# Power_Selection_-_Temperature_Sense.net
KiCad netlist of a schematic drawn in Altium Designer
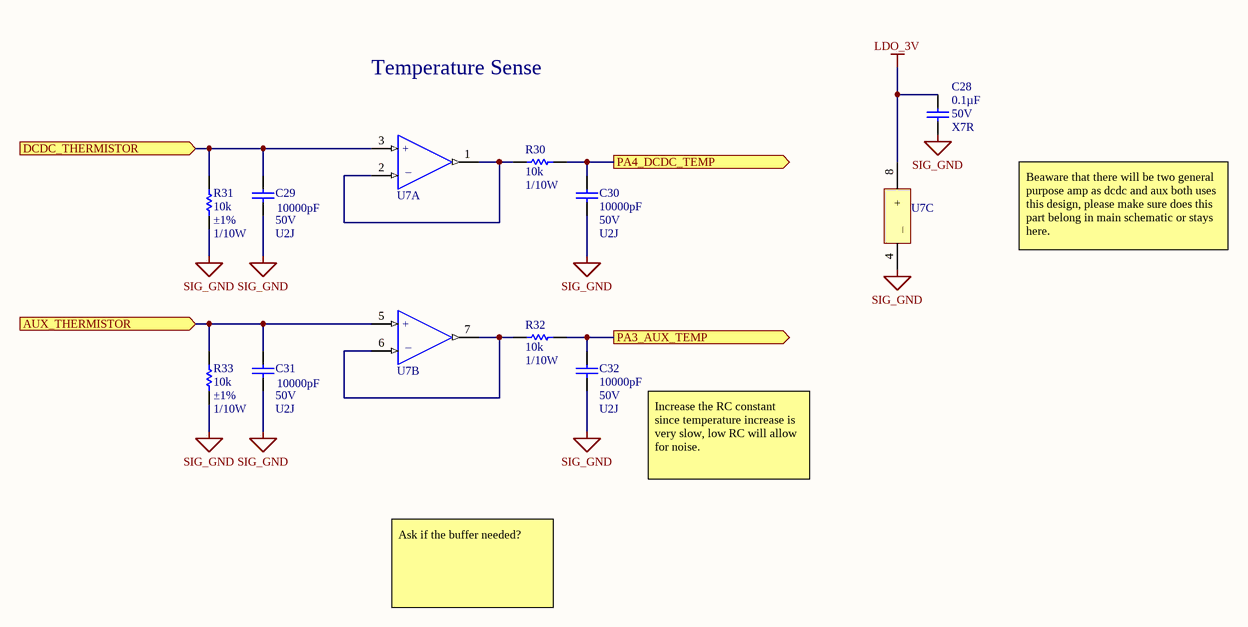
[diagram p0: Power Selection - Temperature Sense.SchDoc]

(export (version "E")
  (design (tool "Eeschema 10.0.6"))
  (components
    (comp (ref "C28")
      (value "CAP CER 0.1UF 50V 10% X7R 0603")
      (footprint "CAP, 0603")
      (description "0.10µF ±10% 50V Ceramic Capacitor X7R 0603 (1608 Metric)")
      (fields
        (field (name "TOLERANCE") "±10%")
        (field (name "CAPACITANCE") "0.1µF")
        (field (name "VOLTAGE") "50V")
        (field (name "TEMPERATURE COEFFICIENT") "X7R")
      )
      (libsource (lib "Schematic Diagrams") (part "CAP CER 0.1UF 50V 10% X7R 0603"))
    )
    (comp (ref "C29")
      (value "CAP CER 10nF 50V 5% X7R 0603")
      (footprint "CAP, 0603")
      (description "10000pF ±5% 50V Ceramic Capacitor U2J 0603 (1608 Metric)")
      (fields
        (field (name "TOLERANCE") "±5%")
        (field (name "CAPACITANCE") "10000pF")
        (field (name "VOLTAGE") "50V")
        (field (name "TEMPERATURE COEFFICIENT") "U2J")
      )
      (libsource (lib "Schematic Diagrams") (part "CAP CER 10nF 50V 5% X7R 0603"))
    )
    (comp (ref "C30")
      (value "CAP CER 10nF 50V 5% X7R 0603")
      (footprint "CAP, 0603")
      (description "10000pF ±5% 50V Ceramic Capacitor U2J 0603 (1608 Metric)")
      (fields
        (field (name "TOLERANCE") "±5%")
        (field (name "CAPACITANCE") "10000pF")
        (field (name "VOLTAGE") "50V")
        (field (name "TEMPERATURE COEFFICIENT") "U2J")
      )
      (libsource (lib "Schematic Diagrams") (part "CAP CER 10nF 50V 5% X7R 0603"))
    )
    (comp (ref "C31")
      (value "CAP CER 10nF 50V 5% X7R 0603")
      (footprint "CAP, 0603")
      (description "10000pF ±5% 50V Ceramic Capacitor U2J 0603 (1608 Metric)")
      (fields
        (field (name "TOLERANCE") "±5%")
        (field (name "CAPACITANCE") "10000pF")
        (field (name "VOLTAGE") "50V")
        (field (name "TEMPERATURE COEFFICIENT") "U2J")
      )
      (libsource (lib "Schematic Diagrams") (part "CAP CER 10nF 50V 5% X7R 0603"))
    )
    (comp (ref "C32")
      (value "CAP CER 10nF 50V 5% X7R 0603")
      (footprint "CAP, 0603")
      (description "10000pF ±5% 50V Ceramic Capacitor U2J 0603 (1608 Metric)")
      (fields
        (field (name "TOLERANCE") "±5%")
        (field (name "CAPACITANCE") "10000pF")
        (field (name "VOLTAGE") "50V")
        (field (name "TEMPERATURE COEFFICIENT") "U2J")
      )
      (libsource (lib "Schematic Diagrams") (part "CAP CER 10nF 50V 5% X7R 0603"))
    )
    (comp (ref "R30")
      (value "RES 10K OHM 1% 1/10W 0603")
      (footprint "RES, 0603")
      (description "RES SMD 10K OHM 1% 1/10W 0603")
      (fields
        (field (name "TOLERANCE") "±1%")
        (field (name "RESISTANCE") "10k")
        (field (name "POWER") "1/10W")
      )
      (libsource (lib "Schematic Diagrams") (part "RES 10K OHM 1% 1/10W 0603"))
    )
    (comp (ref "R31")
      (value "RES 10K OHM 1% 1/10W 0603")
      (footprint "RES, 0603")
      (description "RES SMD 10K OHM 1% 1/10W 0603")
      (fields
        (field (name "RESISTANCE") "10k")
        (field (name "TOLERANCE") "±1%")
        (field (name "POWER") "1/10W")
      )
      (libsource (lib "Schematic Diagrams") (part "RES 10K OHM 1% 1/10W 0603"))
    )
    (comp (ref "R32")
      (value "RES 10K OHM 1% 1/10W 0603")
      (footprint "RES, 0603")
      (description "RES SMD 10K OHM 1% 1/10W 0603")
      (fields
        (field (name "TOLERANCE") "±1%")
        (field (name "RESISTANCE") "10k")
        (field (name "POWER") "1/10W")
      )
      (libsource (lib "Schematic Diagrams") (part "RES 10K OHM 1% 1/10W 0603"))
    )
    (comp (ref "R33")
      (value "RES 10K OHM 1% 1/10W 0603")
      (footprint "RES, 0603")
      (description "RES SMD 10K OHM 1% 1/10W 0603")
      (fields
        (field (name "RESISTANCE") "10k")
        (field (name "TOLERANCE") "±1%")
        (field (name "POWER") "1/10W")
      )
      (libsource (lib "Schematic Diagrams") (part "RES 10K OHM 1% 1/10W 0603"))
    )
    (comp (ref "U7")
      (value "IC OP AMP DUAL GP RR 10MHZ 8-VSSOP")
      (footprint "IC DUAL OPAMP OPA2197 8-VSSOP")
      (description "General Purpose Amplifier 2 Circuit Rail-to-Rail 8-VSSOP")
      (fields
        (field (name "MANUFACTURER") "Texas Instruments")
        (field (name "MANUFACTURER PART NUMBER") "OPA2197IDGKR")
      )
      (libsource (lib "Schematic Diagrams") (part "IC OP AMP DUAL GP RR 10MHZ 8-VSSOP"))
    )
  )
  (nets
    (net (code "1") (name "/AUX_THERMISTOR") (class "Default")
      (node (ref "C31") (pin "1") (pinfunction "1_1") (pintype "passive"))
      (node (ref "R33") (pin "1") (pinfunction "1_1") (pintype "passive"))
      (node (ref "U7") (pin "5") (pinfunction "+IN_B_5") (pintype "input"))
    )
    (net (code "2") (name "/DCDC_THERMISTOR") (class "Default")
      (node (ref "C29") (pin "1") (pinfunction "1_1") (pintype "passive"))
      (node (ref "R31") (pin "1") (pinfunction "1_1") (pintype "passive"))
      (node (ref "U7") (pin "3") (pinfunction "+IN_A_3") (pintype "input"))
    )
    (net (code "3") (name "/PA3_AUX_TEMP") (class "Default")
      (node (ref "C32") (pin "1") (pinfunction "1_1") (pintype "passive"))
      (node (ref "R32") (pin "2") (pinfunction "2_2") (pintype "passive"))
    )
    (net (code "4") (name "/PA4_DCDC_TEMP") (class "Default")
      (node (ref "C30") (pin "1") (pinfunction "1_1") (pintype "passive"))
      (node (ref "R30") (pin "2") (pinfunction "2_2") (pintype "passive"))
    )
    (net (code "5") (name "LDO_3V") (class "Default")
      (node (ref "C28") (pin "1") (pinfunction "1_1") (pintype "passive"))
      (node (ref "U7") (pin "8") (pinfunction "+_8") (pintype "power_in"))
    )
    (net (code "6") (name "Net-(U7A--IN_A)") (class "Default")
      (node (ref "R30") (pin "1") (pinfunction "1_1") (pintype "passive"))
      (node (ref "U7") (pin "1") (pinfunction "OUT_A_1") (pintype "output"))
      (node (ref "U7") (pin "2") (pinfunction "-IN_A_2") (pintype "input"))
    )
    (net (code "7") (name "Net-(U7B--IN_B)") (class "Default")
      (node (ref "R32") (pin "1") (pinfunction "1_1") (pintype "passive"))
      (node (ref "U7") (pin "6") (pinfunction "-IN_B_6") (pintype "input"))
      (node (ref "U7") (pin "7") (pinfunction "OUT_B_7") (pintype "output"))
    )
    (net (code "8") (name "SIG_GND") (class "Default")
      (node (ref "C28") (pin "2") (pinfunction "2_2") (pintype "passive"))
      (node (ref "C29") (pin "2") (pinfunction "2_2") (pintype "passive"))
      (node (ref "C30") (pin "2") (pinfunction "2_2") (pintype "passive"))
      (node (ref "C31") (pin "2") (pinfunction "2_2") (pintype "passive"))
      (node (ref "C32") (pin "2") (pinfunction "2_2") (pintype "passive"))
      (node (ref "R31") (pin "2") (pinfunction "2_2") (pintype "passive"))
      (node (ref "R33") (pin "2") (pinfunction "2_2") (pintype "passive"))
      (node (ref "U7") (pin "4") (pinfunction "__4") (pintype "power_in"))
    )
  )
)
